# Nueron.net
KiCad netlist of a schematic drawn in Altium Designer
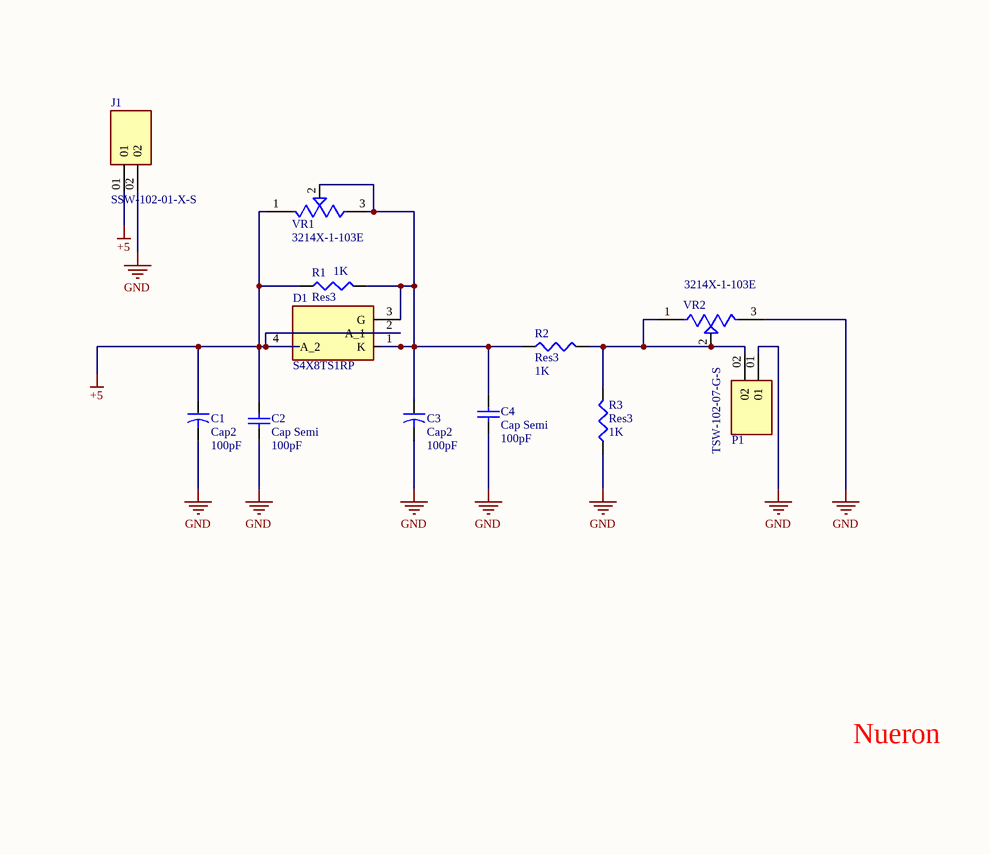
[diagram p0: Nueron.SchDoc, left]
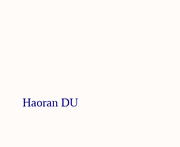
[diagram p1: Nueron.SchDoc, right]

(export (version "E")
  (design (tool "Eeschema 10.0.6"))
  (components
    (comp (ref "C1")
      (value "Cap2")
      (footprint "CAPR5-4X5")
      (description "Capacitor")
      (fields (field (name "ALTIUM_VALUE") "100pF") (field (name "PUBLISHER") "Altium Limited"))
      (libsource (lib "Miscellaneous Devices") (part "Cap2"))
    )
    (comp (ref "C2")
      (value "Cap Semi")
      (footprint "C1206")
      (description "Capacitor (Semiconductor SIM Model)")
      (fields (field (name "ALTIUM_VALUE") "100pF") (field (name "PUBLISHER") "Altium Limited"))
      (libsource (lib "Miscellaneous Devices") (part "Cap Semi"))
    )
    (comp (ref "C3")
      (value "Cap2")
      (footprint "CAPR5-4X5")
      (description "Capacitor")
      (fields (field (name "ALTIUM_VALUE") "100pF") (field (name "PUBLISHER") "Altium Limited"))
      (libsource (lib "Miscellaneous Devices") (part "Cap2"))
    )
    (comp (ref "C4")
      (value "Cap Semi")
      (footprint "C1206")
      (description "Capacitor (Semiconductor SIM Model)")
      (fields (field (name "ALTIUM_VALUE") "100pF") (field (name "PUBLISHER") "Altium Limited"))
      (libsource (lib "Miscellaneous Devices") (part "Cap Semi"))
    )
    (comp (ref "D1")
      (value "S4X8TS1RP")
      (footprint "SamacSys:S4X8TS1RP")
      (description "Thyristor")
      (fields (field (name "MOUSER PART NUMBER") "576-S4X8TS1RP"))
      (libsource (lib "SamacSys") (part "S4X8TS1RP"))
    )
    (comp (ref "J1")
      (value "SSW-102-01-X-S")
      (footprint "TSW-102-XX-YY-S")
      (description "2 Position Receptacle Connector Through Hole")
      (fields (field (name "MP") "SSW-102-01-G-S") (field (name "MF") "Samtec"))
      (libsource (lib "SSW-102-01-X-S") (part "SSW-102-01-X-S"))
    )
    (comp (ref "P1")
      (value "TSW-102-07-G-S")
      (footprint "SAMTEC_TSW-102-07-G-S")
      (fields (field (name "MF") "Samtec Inc."))
      (libsource (lib "headerTSW-102-07-G-S") (part "TSW-102-07-G-S"))
    )
    (comp (ref "R1")
      (value "Res3")
      (footprint "J1-0603")
      (description "Resistor")
      (fields (field (name "ALTIUM_VALUE") "1K") (field (name "PUBLISHER") "Altium Limited"))
      (libsource (lib "Miscellaneous Devices") (part "Res3"))
    )
    (comp (ref "R2")
      (value "Res3")
      (footprint "J1-0603")
      (description "Resistor")
      (fields (field (name "ALTIUM_VALUE") "1K") (field (name "PUBLISHER") "Altium Limited"))
      (libsource (lib "Miscellaneous Devices") (part "Res3"))
    )
    (comp (ref "R3")
      (value "Res3")
      (footprint "J1-0603")
      (description "Resistor")
      (fields (field (name "ALTIUM_VALUE") "1K") (field (name "PUBLISHER") "Altium Limited"))
      (libsource (lib "Miscellaneous Devices") (part "Res3"))
    )
    (comp (ref "VR1")
      (value "3214X-1-103E")
      (footprint "3214X1203E")
      (description "10 kOhms 0.25W, 1/4W Gull Wing Surface Mount Trimmer Potentiometer Cermet 5 Turn Top Adjustment")
      (fields (field (name "MF") "Bourns"))
      (libsource (lib "3214X-1-103E") (part "3214X-1-103E"))
    )
    (comp (ref "VR2")
      (value "3214X-1-103E")
      (footprint "3214X1203E")
      (description "10 kOhms 0.25W, 1/4W Gull Wing Surface Mount Trimmer Potentiometer Cermet 5 Turn Top Adjustment")
      (fields (field (name "MF") "Bourns"))
      (libsource (lib "3214X-1-103E") (part "3214X-1-103E"))
    )
  )
  (nets
    (net (code "1") (name "+5") (class "Default")
      (node (ref "C1") (pin "1") (pinfunction "1_1") (pintype "passive"))
      (node (ref "C2") (pin "2") (pinfunction "2_2") (pintype "passive"))
      (node (ref "D1") (pin "2") (pinfunction "A_1_2") (pintype "passive"))
      (node (ref "D1") (pin "4") (pinfunction "A_2_4") (pintype "passive"))
      (node (ref "J1") (pin "01") (pinfunction "01_01") (pintype "passive"))
      (node (ref "R1") (pin "1") (pinfunction "1_1") (pintype "passive"))
      (node (ref "VR1") (pin "1") (pinfunction "CCW_1") (pintype "passive"))
    )
    (net (code "2") (name "GND") (class "Default")
      (node (ref "C1") (pin "2") (pinfunction "2_2") (pintype "passive"))
      (node (ref "C2") (pin "1") (pinfunction "1_1") (pintype "passive"))
      (node (ref "C3") (pin "2") (pinfunction "2_2") (pintype "passive"))
      (node (ref "C4") (pin "1") (pinfunction "1_1") (pintype "passive"))
      (node (ref "J1") (pin "02") (pinfunction "02_02") (pintype "passive"))
      (node (ref "P1") (pin "01") (pinfunction "01_01") (pintype "passive"))
      (node (ref "R3") (pin "1") (pinfunction "1_1") (pintype "passive"))
      (node (ref "VR2") (pin "3") (pinfunction "CW_3") (pintype "passive"))
    )
    (net (code "3") (name "Net-(D1-G)") (class "Default")
      (node (ref "C3") (pin "1") (pinfunction "1_1") (pintype "passive"))
      (node (ref "C4") (pin "2") (pinfunction "2_2") (pintype "passive"))
      (node (ref "D1") (pin "1") (pinfunction "K_1") (pintype "passive"))
      (node (ref "D1") (pin "3") (pinfunction "G_3") (pintype "passive"))
      (node (ref "R1") (pin "2") (pinfunction "2_2") (pintype "passive"))
      (node (ref "R2") (pin "1") (pinfunction "1_1") (pintype "passive"))
      (node (ref "VR1") (pin "2") (pinfunction "WIPER_2") (pintype "passive"))
      (node (ref "VR1") (pin "3") (pinfunction "CW_3") (pintype "passive"))
    )
    (net (code "4") (name "Net-(VR2-CCW)") (class "Default")
      (node (ref "P1") (pin "02") (pinfunction "02_02") (pintype "passive"))
      (node (ref "R2") (pin "2") (pinfunction "2_2") (pintype "passive"))
      (node (ref "R3") (pin "2") (pinfunction "2_2") (pintype "passive"))
      (node (ref "VR2") (pin "1") (pinfunction "CCW_1") (pintype "passive"))
      (node (ref "VR2") (pin "2") (pinfunction "WIPER_2") (pintype "passive"))
    )
  )
)
